# Main.net
KiCad netlist of a schematic drawn in EAGLE
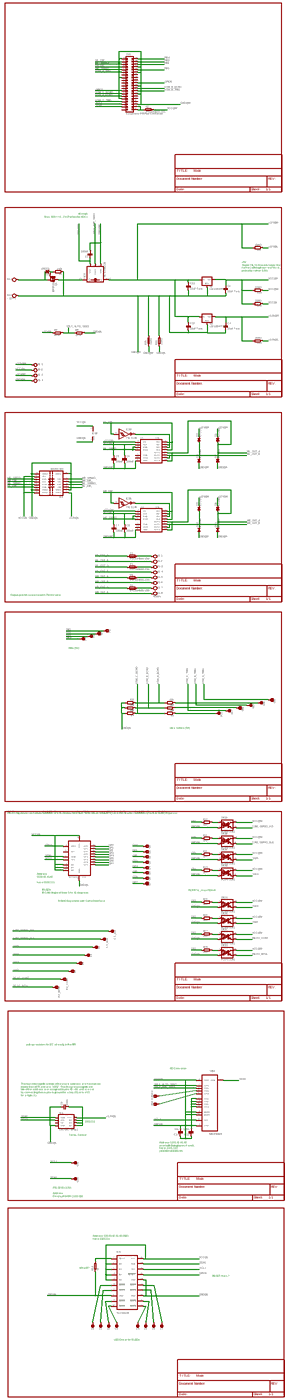
[diagram p0: schematic, sheet 1, overview]
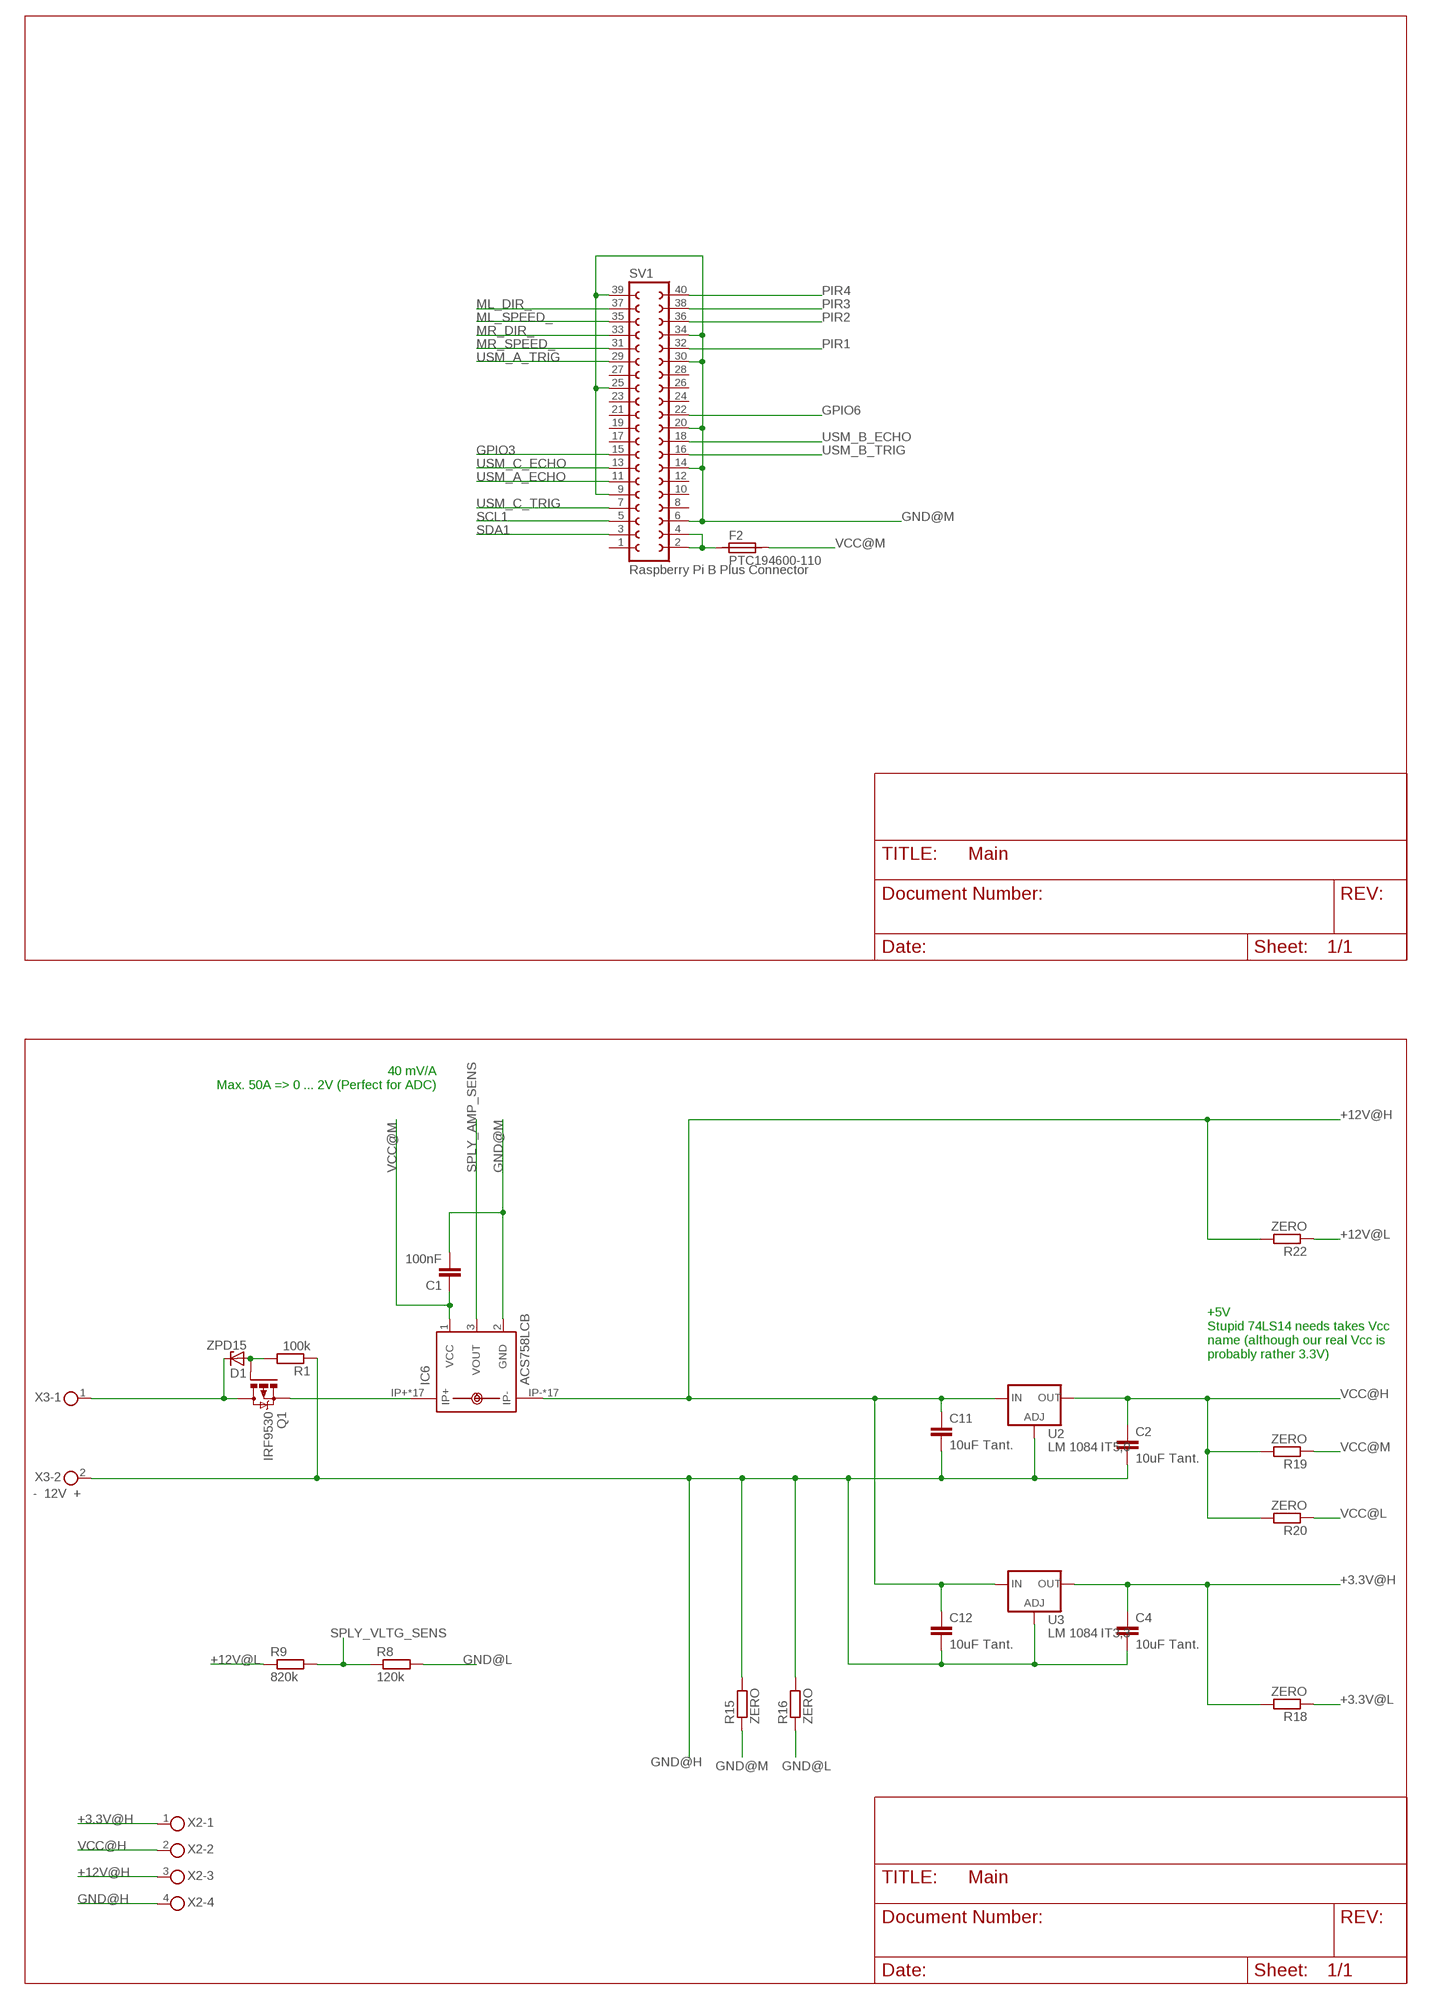
[diagram p1: schematic, sheet 1, part 1 of 4]
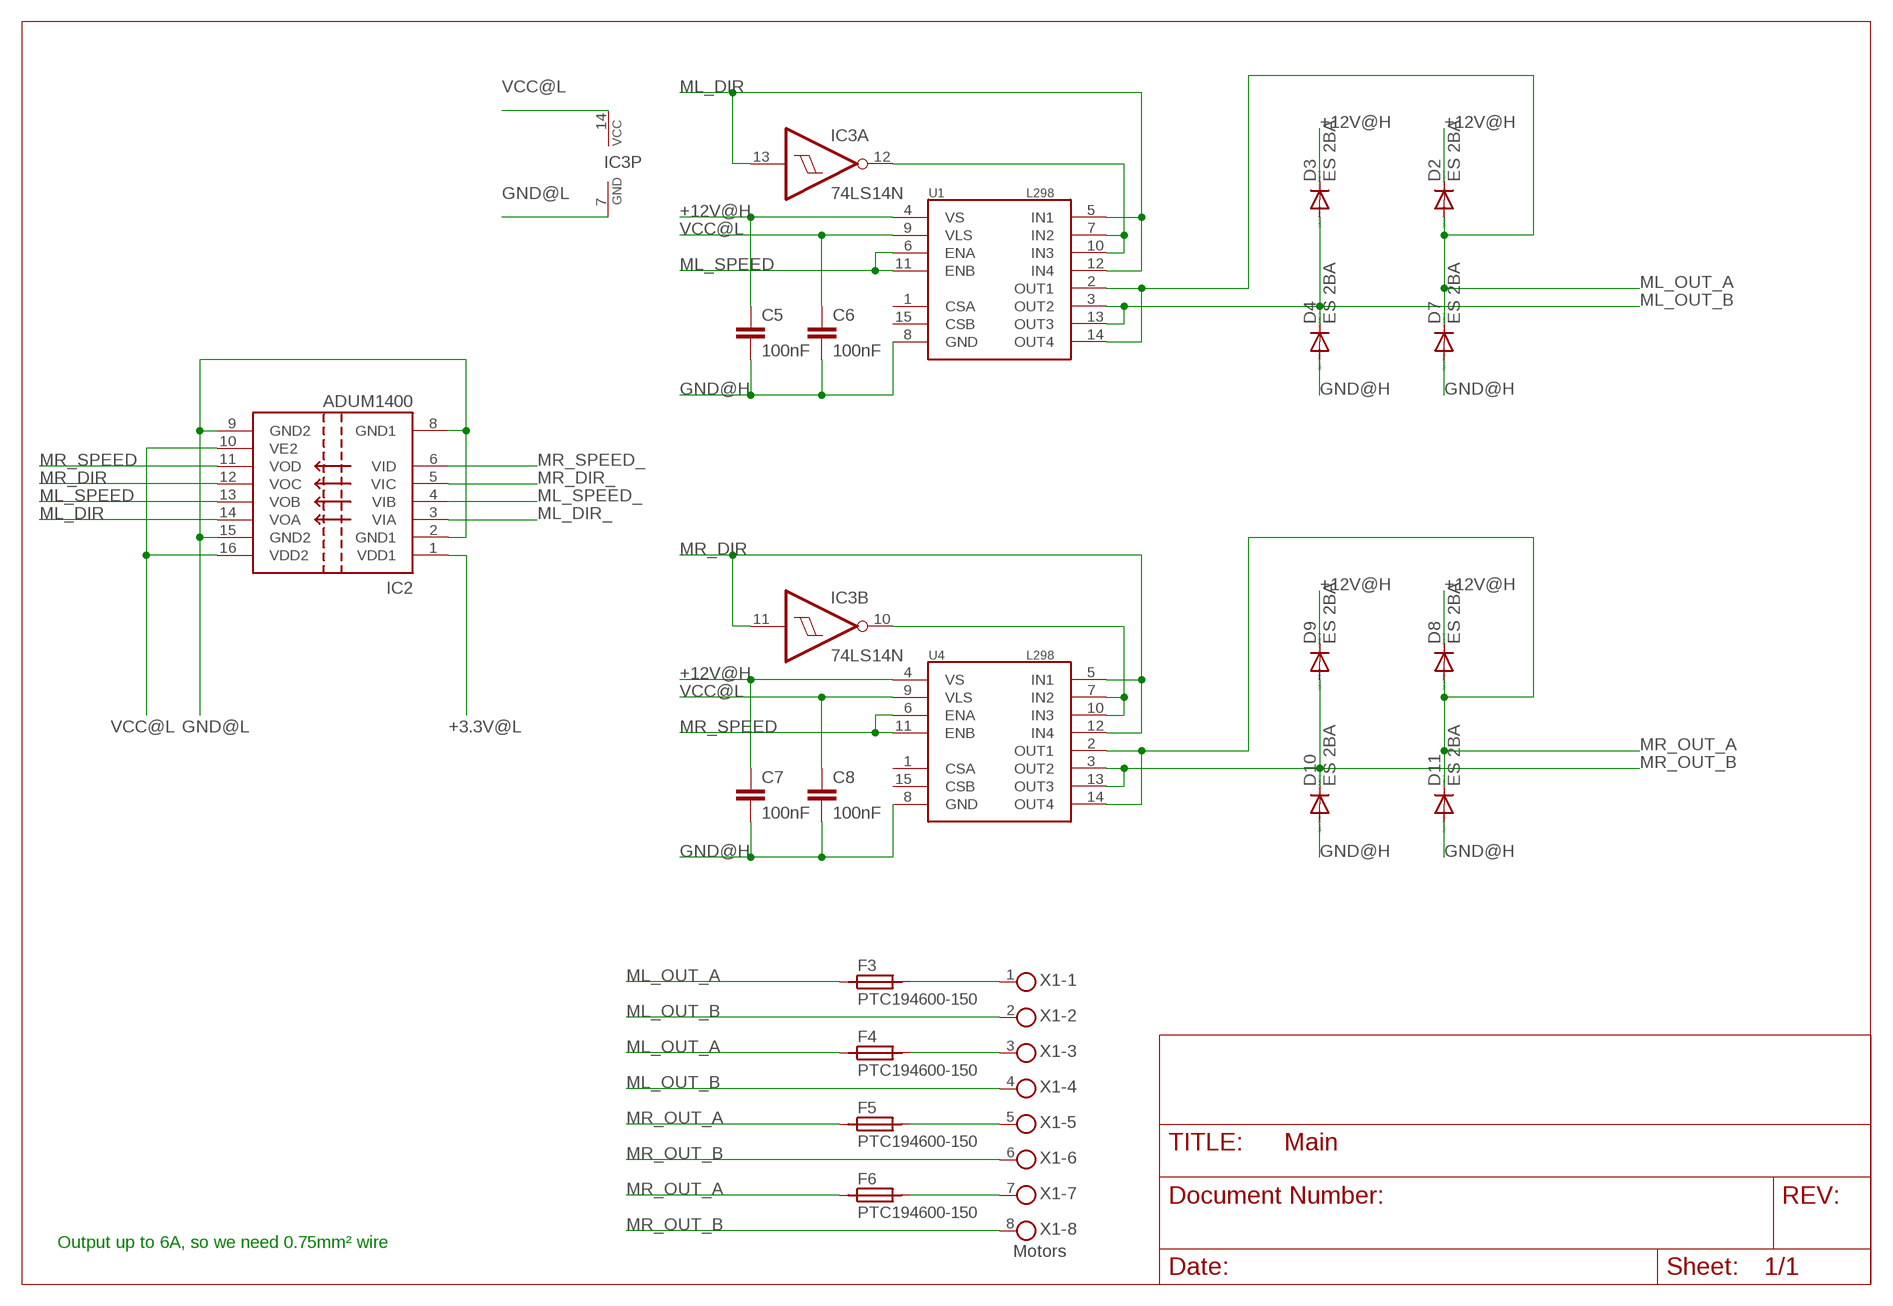
[diagram p2: schematic, sheet 1, part 2 of 4]
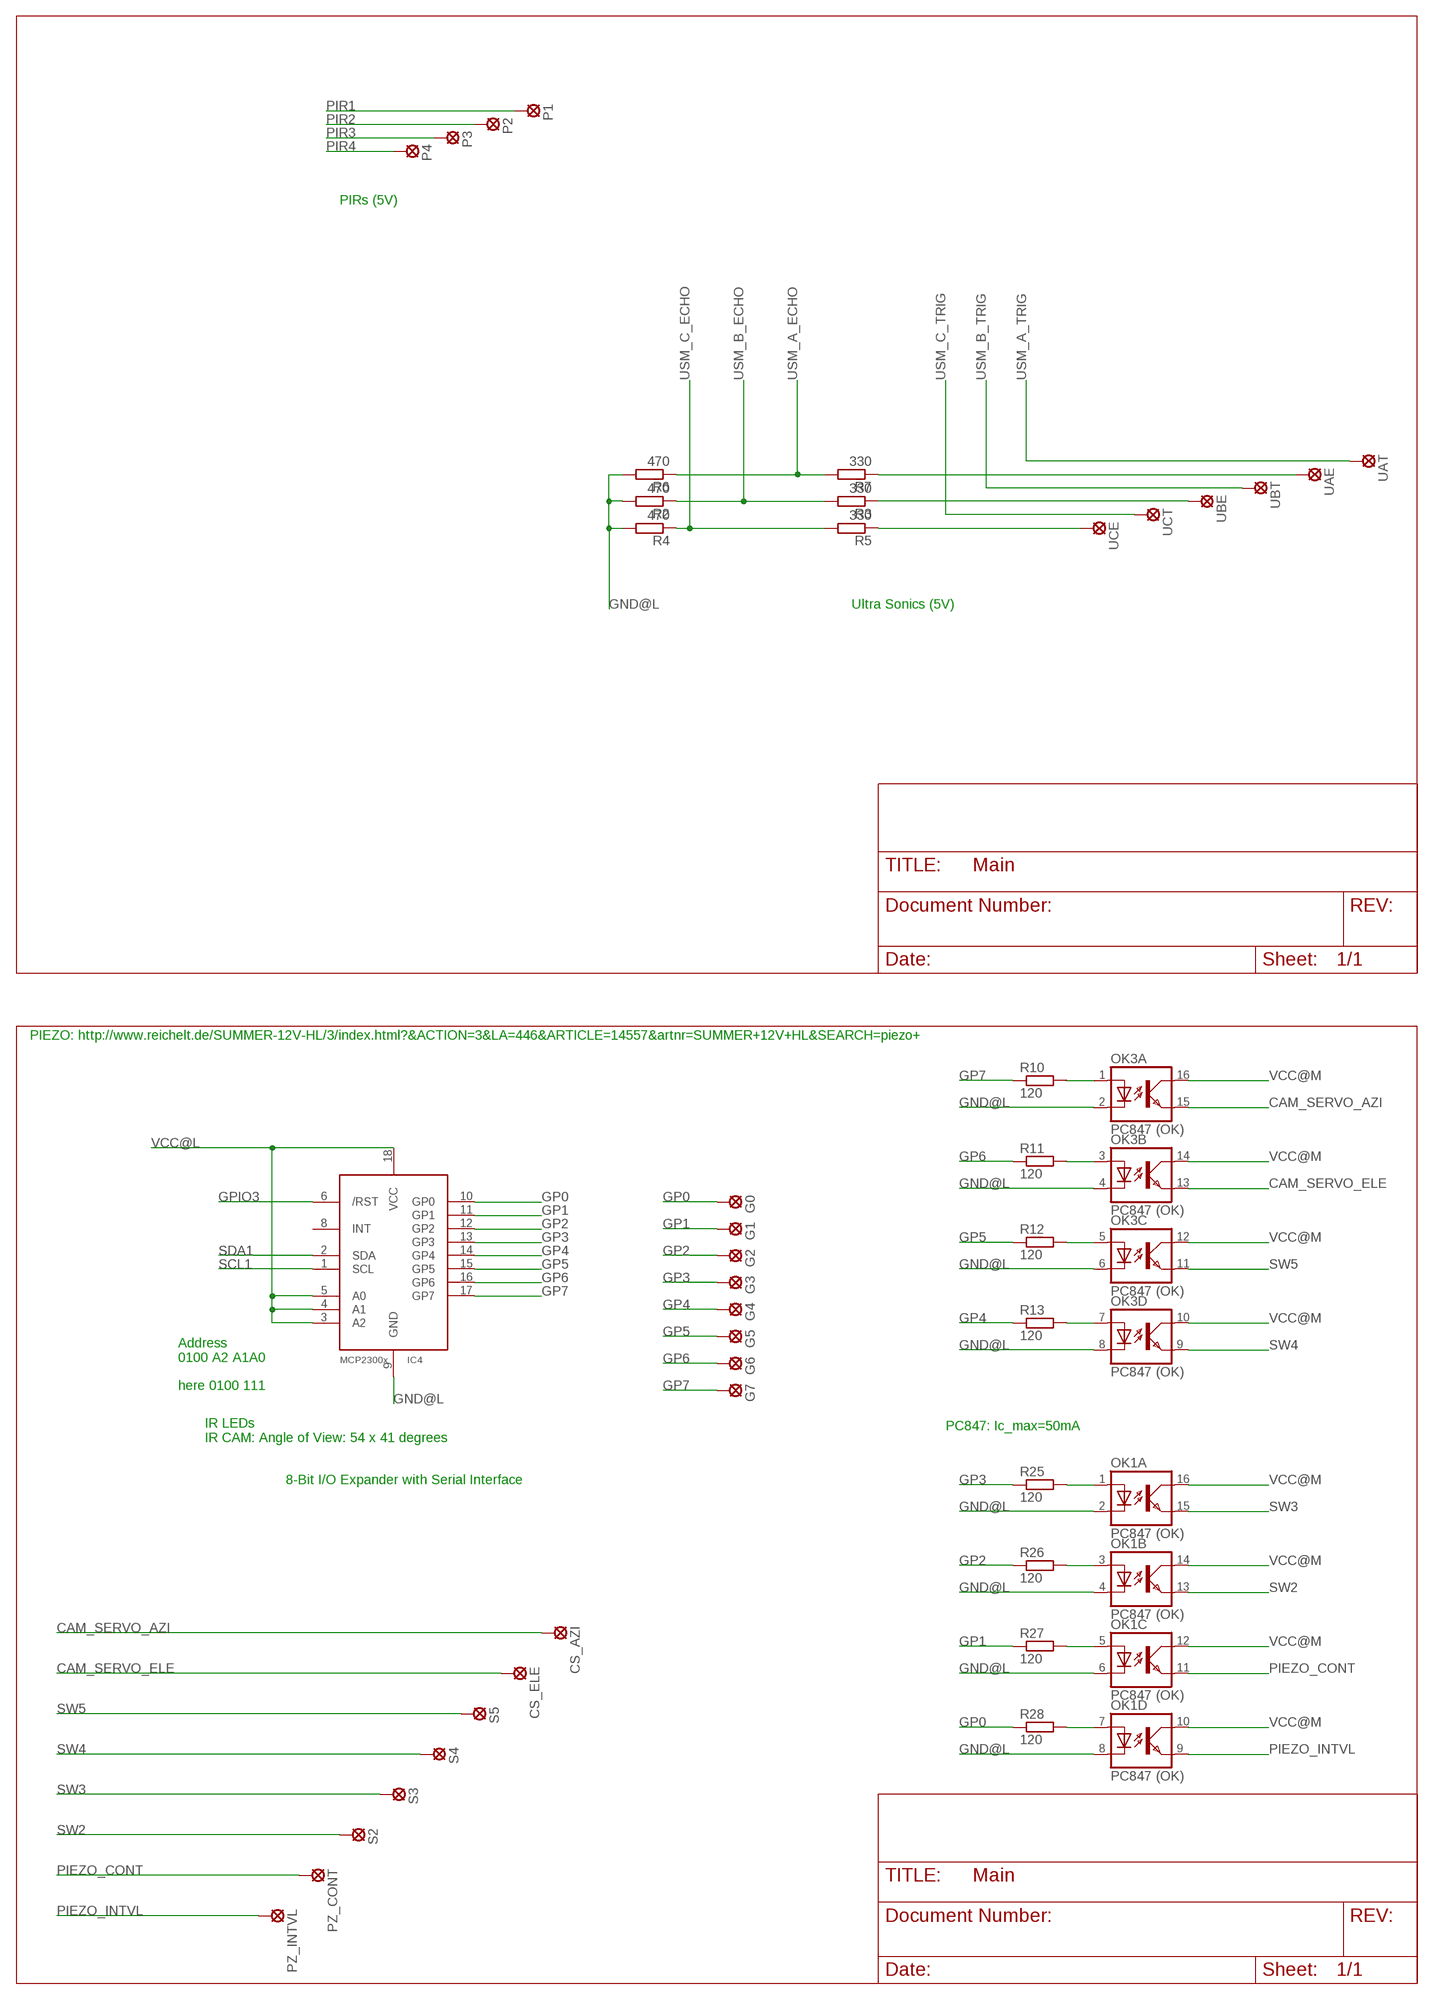
[diagram p3: schematic, sheet 1, part 3 of 4]
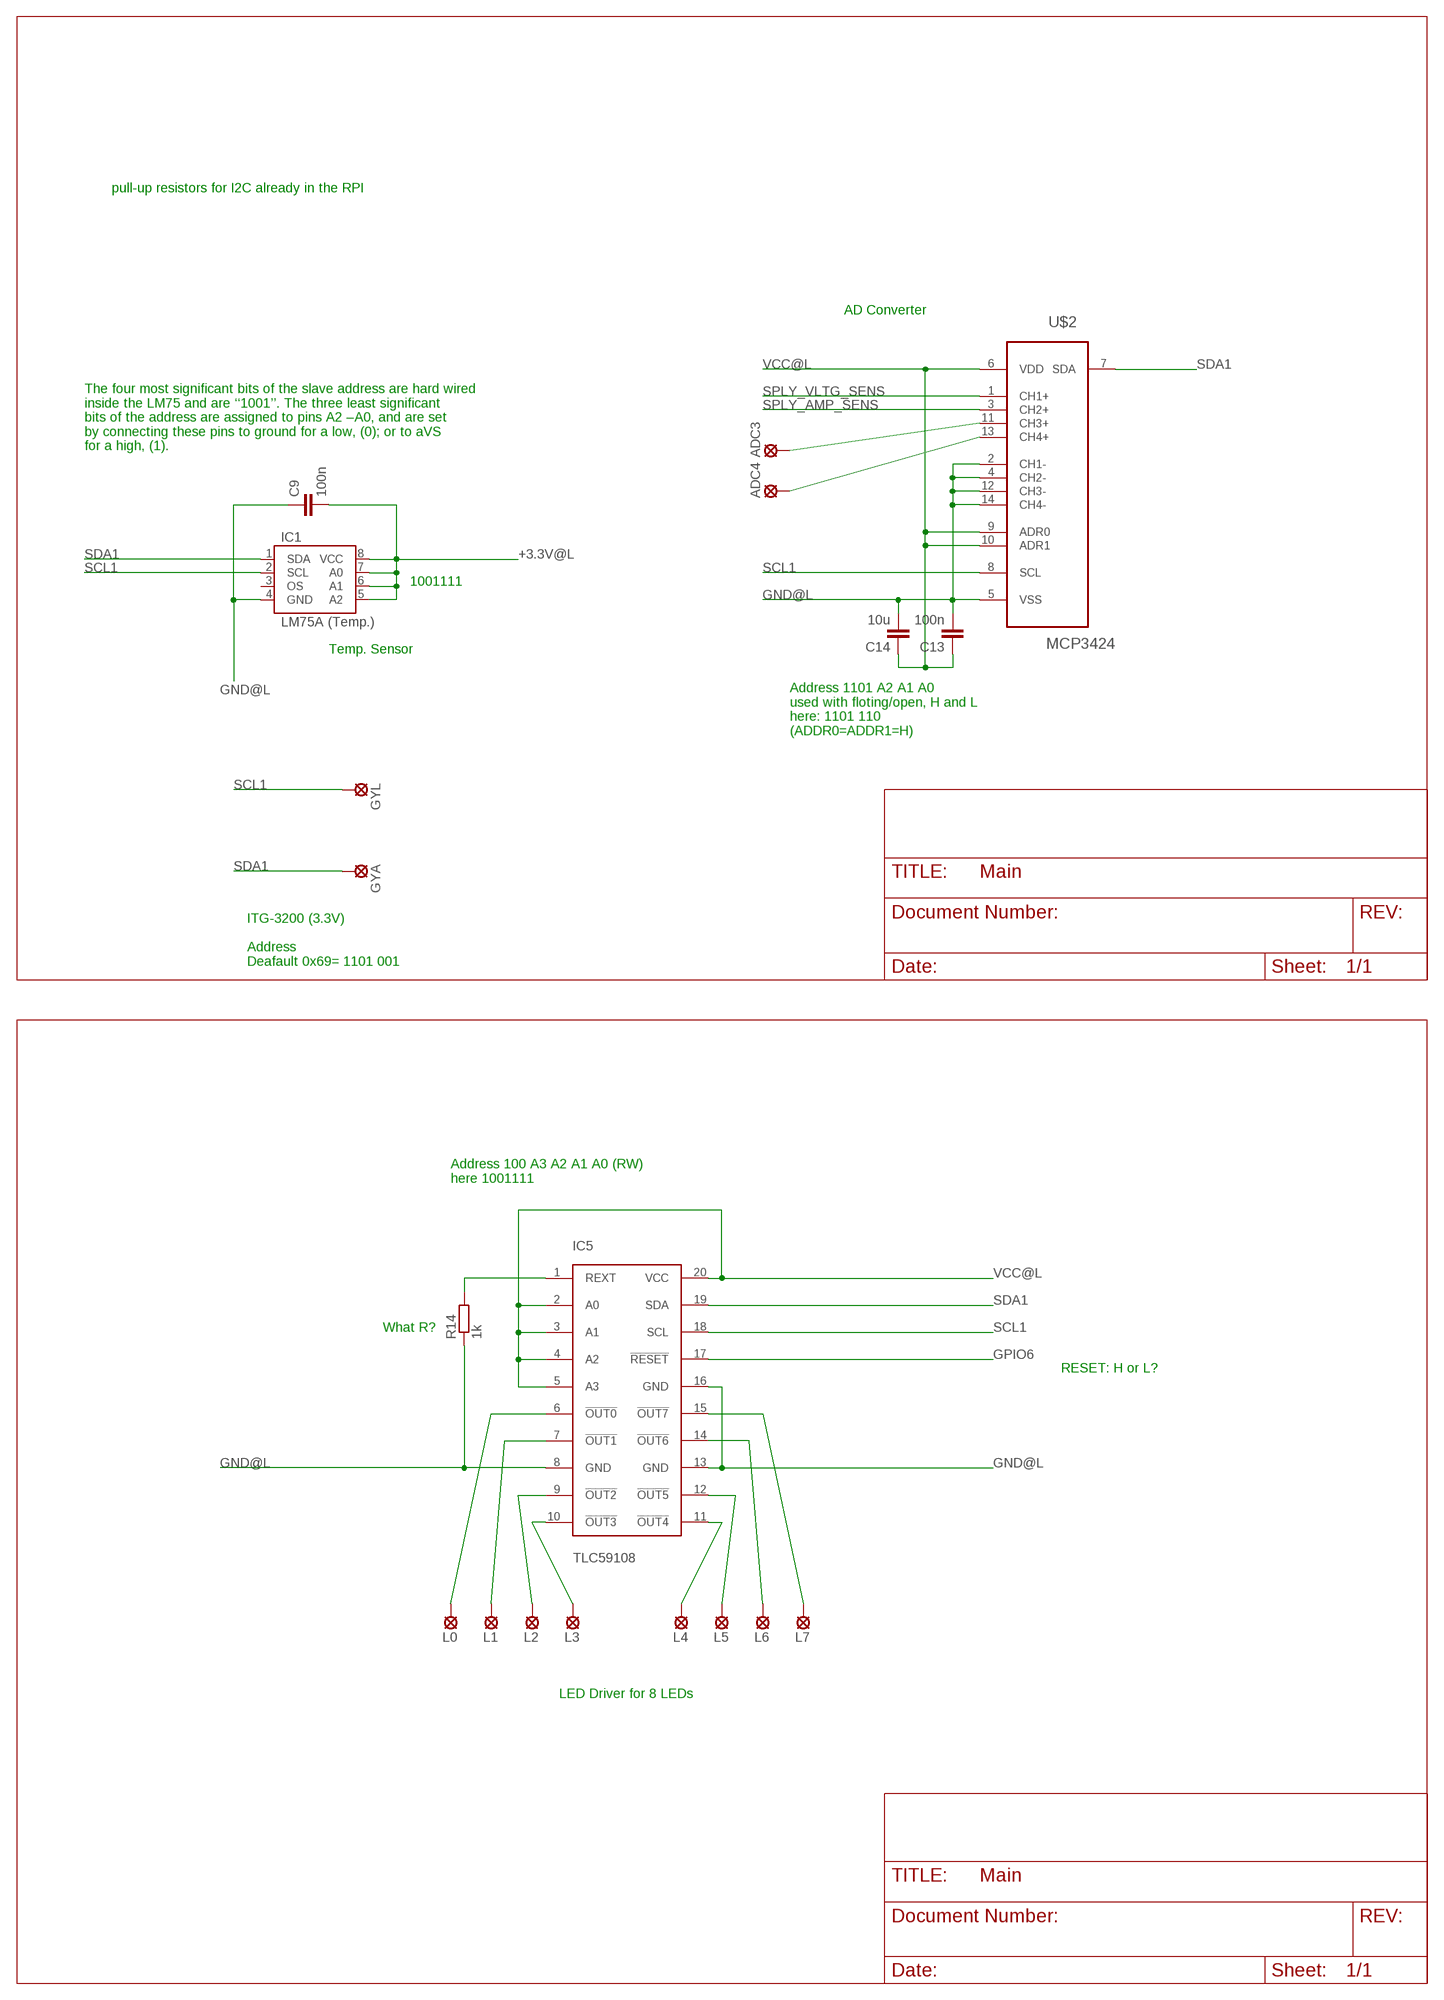
[diagram p4: schematic, sheet 1, part 4 of 4]

(export (version "E")
  (design (tool "Eeschema 10.0.6"))
  (components
    (comp (ref "ADC3")
      (value "LSP10")
      (footprint "eagle-import:LSP10")
      (libsource (lib "eagle-import") (part "LSP10"))
    )
    (comp (ref "ADC4")
      (value "LSP10")
      (footprint "eagle-import:LSP10")
      (libsource (lib "eagle-import") (part "LSP10"))
    )
    (comp (ref "C1")
      (value "100nF")
      (footprint "eagle-import:C0805")
      (libsource (lib "eagle-import") (part "C-EUC0805"))
    )
    (comp (ref "C2")
      (value "10uF Tant.")
      (footprint "eagle-import:C025-040X050")
      (libsource (lib "eagle-import") (part "C-EU025-040X050"))
    )
    (comp (ref "C4")
      (value "10uF Tant.")
      (footprint "eagle-import:C025-040X050")
      (libsource (lib "eagle-import") (part "C-EU025-040X050"))
    )
    (comp (ref "C5")
      (value "100nF")
      (footprint "eagle-import:C0805")
      (libsource (lib "eagle-import") (part "C-EUC0805"))
    )
    (comp (ref "C6")
      (value "100nF")
      (footprint "eagle-import:C0805")
      (libsource (lib "eagle-import") (part "C-EUC0805"))
    )
    (comp (ref "C7")
      (value "100nF")
      (footprint "eagle-import:C0805")
      (libsource (lib "eagle-import") (part "C-EUC0805"))
    )
    (comp (ref "C8")
      (value "100nF")
      (footprint "eagle-import:C0805")
      (libsource (lib "eagle-import") (part "C-EUC0805"))
    )
    (comp (ref "C9")
      (value "100n")
      (footprint "eagle-import:C0805")
      (libsource (lib "eagle-import") (part "C-EUC0805"))
    )
    (comp (ref "C11")
      (value "10uF Tant.")
      (footprint "eagle-import:C025-040X050")
      (libsource (lib "eagle-import") (part "C-EU025-040X050"))
    )
    (comp (ref "C12")
      (value "10uF Tant.")
      (footprint "eagle-import:C025-040X050")
      (libsource (lib "eagle-import") (part "C-EU025-040X050"))
    )
    (comp (ref "C13")
      (value "100n")
      (footprint "eagle-import:C0805")
      (libsource (lib "eagle-import") (part "C-EUC0805"))
    )
    (comp (ref "C14")
      (value "10u")
      (footprint "eagle-import:C0805")
      (libsource (lib "eagle-import") (part "C-EUC0805"))
    )
    (comp (ref "CS_AZI")
      (value "LSP10")
      (footprint "eagle-import:LSP10")
      (libsource (lib "eagle-import") (part "LSP10"))
    )
    (comp (ref "CS_ELE")
      (value "LSP10")
      (footprint "eagle-import:LSP10")
      (libsource (lib "eagle-import") (part "LSP10"))
    )
    (comp (ref "D1")
      (value "ZPD15")
      (footprint "eagle-import:DO35Z10")
      (libsource (lib "eagle-import") (part "ZENER-DIODEDO35Z10"))
    )
    (comp (ref "D2")
      (value "ES 2BA")
      (footprint "eagle-import:SMB")
      (libsource (lib "eagle-import") (part "ES2D"))
    )
    (comp (ref "D3")
      (value "ES 2BA")
      (footprint "eagle-import:SMB")
      (libsource (lib "eagle-import") (part "ES2D"))
    )
    (comp (ref "D4")
      (value "ES 2BA")
      (footprint "eagle-import:SMB")
      (libsource (lib "eagle-import") (part "ES2D"))
    )
    (comp (ref "D7")
      (value "ES 2BA")
      (footprint "eagle-import:SMB")
      (libsource (lib "eagle-import") (part "ES2D"))
    )
    (comp (ref "D8")
      (value "ES 2BA")
      (footprint "eagle-import:SMB")
      (libsource (lib "eagle-import") (part "ES2D"))
    )
    (comp (ref "D9")
      (value "ES 2BA")
      (footprint "eagle-import:SMB")
      (libsource (lib "eagle-import") (part "ES2D"))
    )
    (comp (ref "D10")
      (value "ES 2BA")
      (footprint "eagle-import:SMB")
      (libsource (lib "eagle-import") (part "ES2D"))
    )
    (comp (ref "D11")
      (value "ES 2BA")
      (footprint "eagle-import:SMB")
      (libsource (lib "eagle-import") (part "ES2D"))
    )
    (comp (ref "F2")
      (value "PTC194600-110")
      (footprint "eagle-import:1820")
      (libsource (lib "eagle-import") (part "SIBA194600"))
    )
    (comp (ref "F3")
      (value "PTC194600-150")
      (footprint "eagle-import:1820")
      (libsource (lib "eagle-import") (part "SIBA194600"))
    )
    (comp (ref "F4")
      (value "PTC194600-150")
      (footprint "eagle-import:1820")
      (libsource (lib "eagle-import") (part "SIBA194600"))
    )
    (comp (ref "F5")
      (value "PTC194600-150")
      (footprint "eagle-import:1820")
      (libsource (lib "eagle-import") (part "SIBA194600"))
    )
    (comp (ref "F6")
      (value "PTC194600-150")
      (footprint "eagle-import:1820")
      (libsource (lib "eagle-import") (part "SIBA194600"))
    )
    (comp (ref "G0")
      (value "LSP10")
      (footprint "eagle-import:LSP10")
      (libsource (lib "eagle-import") (part "LSP10"))
    )
    (comp (ref "G1")
      (value "LSP10")
      (footprint "eagle-import:LSP10")
      (libsource (lib "eagle-import") (part "LSP10"))
    )
    (comp (ref "G2")
      (value "LSP10")
      (footprint "eagle-import:LSP10")
      (libsource (lib "eagle-import") (part "LSP10"))
    )
    (comp (ref "G3")
      (value "LSP10")
      (footprint "eagle-import:LSP10")
      (libsource (lib "eagle-import") (part "LSP10"))
    )
    (comp (ref "G4")
      (value "LSP10")
      (footprint "eagle-import:LSP10")
      (libsource (lib "eagle-import") (part "LSP10"))
    )
    (comp (ref "G5")
      (value "LSP10")
      (footprint "eagle-import:LSP10")
      (libsource (lib "eagle-import") (part "LSP10"))
    )
    (comp (ref "G6")
      (value "LSP10")
      (footprint "eagle-import:LSP10")
      (libsource (lib "eagle-import") (part "LSP10"))
    )
    (comp (ref "G7")
      (value "LSP10")
      (footprint "eagle-import:LSP10")
      (libsource (lib "eagle-import") (part "LSP10"))
    )
    (comp (ref "GYA")
      (value "LSP10")
      (footprint "eagle-import:LSP10")
      (libsource (lib "eagle-import") (part "LSP10"))
    )
    (comp (ref "GYL")
      (value "GYRO_SCL")
      (footprint "eagle-import:LSP10")
      (libsource (lib "eagle-import") (part "LSP10"))
    )
    (comp (ref "IC1")
      (value "LM75A (Temp.)")
      (footprint "eagle-import:SO8")
      (libsource (lib "eagle-import") (part "LM75A"))
    )
    (comp (ref "IC2")
      (value "ADUM1400")
      (footprint "eagle-import:SO16W")
      (libsource (lib "eagle-import") (part "ADUM1400"))
    )
    (comp (ref "IC3")
      (value "74LS14N")
      (footprint "eagle-import:DIL14")
      (libsource (lib "eagle-import") (part "7414NLS"))
    )
    (comp (ref "IC4")
      (value "MCP2300X/P")
      (footprint "eagle-import:DIL18")
      (libsource (lib "eagle-import") (part "MCP2300X/P"))
    )
    (comp (ref "IC5")
      (value "TLC59108")
      (footprint "eagle-import:TSSOP20")
      (libsource (lib "eagle-import") (part "TLC59108"))
    )
    (comp (ref "IC6")
      (value "ACS758LCB")
      (footprint "eagle-import:CB-PFF")
      (fields (field (name "MPN") "ACS758LCB-050B-PFF-T"))
      (libsource (lib "eagle-import") (part "ACS758LCB-050B-PFF-T"))
    )
    (comp (ref "L0")
      (value "LSP10")
      (footprint "eagle-import:LSP10")
      (libsource (lib "eagle-import") (part "LSP10"))
    )
    (comp (ref "L1")
      (value "LSP10")
      (footprint "eagle-import:LSP10")
      (libsource (lib "eagle-import") (part "LSP10"))
    )
    (comp (ref "L2")
      (value "LSP10")
      (footprint "eagle-import:LSP10")
      (libsource (lib "eagle-import") (part "LSP10"))
    )
    (comp (ref "L3")
      (value "LSP10")
      (footprint "eagle-import:LSP10")
      (libsource (lib "eagle-import") (part "LSP10"))
    )
    (comp (ref "L4")
      (value "LSP10")
      (footprint "eagle-import:LSP10")
      (libsource (lib "eagle-import") (part "LSP10"))
    )
    (comp (ref "L5")
      (value "LSP10")
      (footprint "eagle-import:LSP10")
      (libsource (lib "eagle-import") (part "LSP10"))
    )
    (comp (ref "L6")
      (value "LSP10")
      (footprint "eagle-import:LSP10")
      (libsource (lib "eagle-import") (part "LSP10"))
    )
    (comp (ref "L7")
      (value "LSP10")
      (footprint "eagle-import:LSP10")
      (libsource (lib "eagle-import") (part "LSP10"))
    )
    (comp (ref "OK1")
      (value "PC847 (OK)")
      (footprint "eagle-import:DIL16")
      (libsource (lib "eagle-import") (part "PC847"))
    )
    (comp (ref "OK3")
      (value "PC847 (OK)")
      (footprint "eagle-import:DIL16")
      (libsource (lib "eagle-import") (part "PC847"))
    )
    (comp (ref "P1")
      (value "LSP10")
      (footprint "eagle-import:LSP10")
      (libsource (lib "eagle-import") (part "LSP10"))
    )
    (comp (ref "P2")
      (value "LSP10")
      (footprint "eagle-import:LSP10")
      (libsource (lib "eagle-import") (part "LSP10"))
    )
    (comp (ref "P3")
      (value "LSP10")
      (footprint "eagle-import:LSP10")
      (libsource (lib "eagle-import") (part "LSP10"))
    )
    (comp (ref "P4")
      (value "LSP10")
      (footprint "eagle-import:LSP10")
      (libsource (lib "eagle-import") (part "LSP10"))
    )
    (comp (ref "PZ_CONT")
      (value "LSP10")
      (footprint "eagle-import:LSP10")
      (libsource (lib "eagle-import") (part "LSP10"))
    )
    (comp (ref "PZ_INTVL")
      (value "LSP10")
      (footprint "eagle-import:LSP10")
      (libsource (lib "eagle-import") (part "LSP10"))
    )
    (comp (ref "Q1")
      (value "IRF9530")
      (footprint "eagle-import:TO220BV")
      (libsource (lib "eagle-import") (part "IRF9530"))
    )
    (comp (ref "R1")
      (value "100k")
      (footprint "eagle-import:R0805")
      (libsource (lib "eagle-import") (part "resistor_R-EU_R0805"))
    )
    (comp (ref "R2")
      (value "470")
      (footprint "eagle-import:R0603")
      (libsource (lib "eagle-import") (part "resistor_R-EU_R0603"))
    )
    (comp (ref "R3")
      (value "330")
      (footprint "eagle-import:R0603")
      (libsource (lib "eagle-import") (part "resistor_R-EU_R0603"))
    )
    (comp (ref "R4")
      (value "470")
      (footprint "eagle-import:R0603")
      (libsource (lib "eagle-import") (part "resistor_R-EU_R0603"))
    )
    (comp (ref "R5")
      (value "330")
      (footprint "eagle-import:R0603")
      (libsource (lib "eagle-import") (part "resistor_R-EU_R0603"))
    )
    (comp (ref "R6")
      (value "470")
      (footprint "eagle-import:R0603")
      (libsource (lib "eagle-import") (part "resistor_R-EU_R0603"))
    )
    (comp (ref "R7")
      (value "330")
      (footprint "eagle-import:R0603")
      (libsource (lib "eagle-import") (part "resistor_R-EU_R0603"))
    )
    (comp (ref "R8")
      (value "120k")
      (footprint "eagle-import:R0603")
      (libsource (lib "eagle-import") (part "rcl-2_R-EU_R0603"))
    )
    (comp (ref "R9")
      (value "820k")
      (footprint "eagle-import:R0603")
      (libsource (lib "eagle-import") (part "rcl-2_R-EU_R0603"))
    )
    (comp (ref "R10")
      (value "120")
      (footprint "eagle-import:R0603")
      (libsource (lib "eagle-import") (part "resistor_R-EU_R0603"))
    )
    (comp (ref "R11")
      (value "120")
      (footprint "eagle-import:R0603")
      (libsource (lib "eagle-import") (part "resistor_R-EU_R0603"))
    )
    (comp (ref "R12")
      (value "120")
      (footprint "eagle-import:R0603")
      (libsource (lib "eagle-import") (part "resistor_R-EU_R0603"))
    )
    (comp (ref "R13")
      (value "120")
      (footprint "eagle-import:R0603")
      (libsource (lib "eagle-import") (part "resistor_R-EU_R0603"))
    )
    (comp (ref "R14")
      (value "1k")
      (footprint "eagle-import:R0603")
      (libsource (lib "eagle-import") (part "R-EU_R0603"))
    )
    (comp (ref "R15")
      (value "ZERO")
      (footprint "eagle-import:0204V")
      (libsource (lib "eagle-import") (part "resistor_R-EU_0204/2V"))
    )
    (comp (ref "R16")
      (value "ZERO")
      (footprint "eagle-import:0204V")
      (libsource (lib "eagle-import") (part "resistor_R-EU_0204/2V"))
    )
    (comp (ref "R18")
      (value "ZERO")
      (footprint "eagle-import:0204V")
      (libsource (lib "eagle-import") (part "resistor_R-EU_0204/2V"))
    )
    (comp (ref "R19")
      (value "ZERO")
      (footprint "eagle-import:0204V")
      (libsource (lib "eagle-import") (part "resistor_R-EU_0204/2V"))
    )
    (comp (ref "R20")
      (value "ZERO")
      (footprint "eagle-import:0204V")
      (libsource (lib "eagle-import") (part "resistor_R-EU_0204/2V"))
    )
    (comp (ref "R22")
      (value "ZERO")
      (footprint "eagle-import:0204V")
      (libsource (lib "eagle-import") (part "resistor_R-EU_0204/2V"))
    )
    (comp (ref "R25")
      (value "120")
      (footprint "eagle-import:R0603")
      (libsource (lib "eagle-import") (part "resistor_R-EU_R0603"))
    )
    (comp (ref "R26")
      (value "120")
      (footprint "eagle-import:R0603")
      (libsource (lib "eagle-import") (part "resistor_R-EU_R0603"))
    )
    (comp (ref "R27")
      (value "120")
      (footprint "eagle-import:R0603")
      (libsource (lib "eagle-import") (part "resistor_R-EU_R0603"))
    )
    (comp (ref "R28")
      (value "120")
      (footprint "eagle-import:R0603")
      (libsource (lib "eagle-import") (part "resistor_R-EU_R0603"))
    )
    (comp (ref "S2")
      (value "LSP10")
      (footprint "eagle-import:LSP10")
      (libsource (lib "eagle-import") (part "LSP10"))
    )
    (comp (ref "S3")
      (value "LSP10")
      (footprint "eagle-import:LSP10")
      (libsource (lib "eagle-import") (part "LSP10"))
    )
    (comp (ref "S4")
      (value "LSP10")
      (footprint "eagle-import:LSP10")
      (libsource (lib "eagle-import") (part "LSP10"))
    )
    (comp (ref "S5")
      (value "LSP10")
      (footprint "eagle-import:LSP10")
      (libsource (lib "eagle-import") (part "LSP10"))
    )
    (comp (ref "SV1")
      (value "Raspberry Pi B Plus Connector")
      (footprint "eagle-import:FE20-2")
      (libsource (lib "eagle-import") (part "FE20-2"))
    )
    (comp (ref "U$2")
      (value "MCP3424")
      (footprint "eagle-import:SOP65P640X120-14N")
      (fields (field (name "MPN") "MCP3424-E/ST"))
      (libsource (lib "eagle-import") (part "MCP3424-E/ST"))
    )
    (comp (ref "U1")
      (value "L298")
      (footprint "eagle-import:MULTIWATT15")
      (libsource (lib "eagle-import") (part "L298"))
    )
    (comp (ref "U2")
      (value "LM 1084 IT5,0")
      (footprint "eagle-import:317TS")
      (libsource (lib "eagle-import") (part "LM1084-V"))
    )
    (comp (ref "U3")
      (value "LM 1084 IT3,3")
      (footprint "eagle-import:317TS")
      (libsource (lib "eagle-import") (part "LM1084-V"))
    )
    (comp (ref "U4")
      (value "L298")
      (footprint "eagle-import:MULTIWATT15")
      (libsource (lib "eagle-import") (part "L298"))
    )
    (comp (ref "UAE")
      (value "LSP10")
      (footprint "eagle-import:LSP10")
      (libsource (lib "eagle-import") (part "LSP10"))
    )
    (comp (ref "UAT")
      (value "LSP10")
      (footprint "eagle-import:LSP10")
      (libsource (lib "eagle-import") (part "LSP10"))
    )
    (comp (ref "UBE")
      (value "LSP10")
      (footprint "eagle-import:LSP10")
      (libsource (lib "eagle-import") (part "LSP10"))
    )
    (comp (ref "UBT")
      (value "LSP10")
      (footprint "eagle-import:LSP10")
      (libsource (lib "eagle-import") (part "LSP10"))
    )
    (comp (ref "UCE")
      (value "LSP10")
      (footprint "eagle-import:LSP10")
      (libsource (lib "eagle-import") (part "LSP10"))
    )
    (comp (ref "UCT")
      (value "LSP10")
      (footprint "eagle-import:LSP10")
      (libsource (lib "eagle-import") (part "LSP10"))
    )
    (comp (ref "X1")
      (value "Motors")
      (footprint "eagle-import:8POL35")
      (libsource (lib "eagle-import") (part "AKL59-08"))
    )
    (comp (ref "X2")
      (value "AKL59-04")
      (footprint "eagle-import:4POL35")
      (libsource (lib "eagle-import") (part "AKL59-04"))
    )
    (comp (ref "X3")
      (value "- 12V +")
      (footprint "eagle-import:2POL35")
      (libsource (lib "eagle-import") (part "AKL59-02"))
    )
  )
  (nets
    (net (code "1") (name "/+3.3V@H") (class "Default")
      (node (ref "C4") (pin "1") (pinfunction "1_1") (pintype "passive"))
      (node (ref "R18") (pin "2") (pinfunction "2_2") (pintype "passive"))
      (node (ref "U3") (pin "2") (pinfunction "OUT_2") (pintype "passive"))
      (node (ref "X2") (pin "1") (pinfunction "1_1") (pintype "passive"))
    )
    (net (code "2") (name "/+3.3V@L") (class "Default")
      (node (ref "C9") (pin "2") (pinfunction "2_2") (pintype "passive"))
      (node (ref "IC1") (pin "5") (pinfunction "A2_5") (pintype "bidirectional"))
      (node (ref "IC1") (pin "6") (pinfunction "A1_6") (pintype "bidirectional"))
      (node (ref "IC1") (pin "7") (pinfunction "A0_7") (pintype "bidirectional"))
      (node (ref "IC1") (pin "8") (pinfunction "VCC_8") (pintype "bidirectional"))
      (node (ref "IC2") (pin "1") (pinfunction "VDD1_1") (pintype "power_in"))
      (node (ref "R18") (pin "1") (pinfunction "1_1") (pintype "passive"))
    )
    (net (code "3") (name "/+12V@H") (class "Default")
      (node (ref "C11") (pin "1") (pinfunction "1_1") (pintype "passive"))
      (node (ref "C12") (pin "1") (pinfunction "1_1") (pintype "passive"))
      (node (ref "C5") (pin "1") (pinfunction "1_1") (pintype "passive"))
      (node (ref "C7") (pin "1") (pinfunction "1_1") (pintype "passive"))
      (node (ref "D2") (pin "C") (pinfunction "C_C") (pintype "passive"))
      (node (ref "D3") (pin "C") (pinfunction "C_C") (pintype "passive"))
      (node (ref "D8") (pin "C") (pinfunction "C_C") (pintype "passive"))
      (node (ref "D9") (pin "C") (pinfunction "C_C") (pintype "passive"))
      (node (ref "IC6") (pin "IP-") (pinfunction "IP-_IP-") (pintype "passive"))
      (node (ref "IC6") (pin "IP-@10") (pinfunction "IP-_IP-@10") (pintype "passive"))
      (node (ref "IC6") (pin "IP-@11") (pinfunction "IP-_IP-@11") (pintype "passive"))
      (node (ref "IC6") (pin "IP-@12") (pinfunction "IP-_IP-@12") (pintype "passive"))
      (node (ref "IC6") (pin "IP-@13") (pinfunction "IP-_IP-@13") (pintype "passive"))
      (node (ref "IC6") (pin "IP-@14") (pinfunction "IP-_IP-@14") (pintype "passive"))
      (node (ref "IC6") (pin "IP-@15") (pinfunction "IP-_IP-@15") (pintype "passive"))
      (node (ref "IC6") (pin "IP-@16") (pinfunction "IP-_IP-@16") (pintype "passive"))
      (node (ref "IC6") (pin "IP-@17") (pinfunction "IP-_IP-@17") (pintype "passive"))
      (node (ref "IC6") (pin "IP-@2") (pinfunction "IP-_IP-@2") (pintype "passive"))
      (node (ref "IC6") (pin "IP-@3") (pinfunction "IP-_IP-@3") (pintype "passive"))
      (node (ref "IC6") (pin "IP-@4") (pinfunction "IP-_IP-@4") (pintype "passive"))
      (node (ref "IC6") (pin "IP-@5") (pinfunction "IP-_IP-@5") (pintype "passive"))
      (node (ref "IC6") (pin "IP-@6") (pinfunction "IP-_IP-@6") (pintype "passive"))
      (node (ref "IC6") (pin "IP-@7") (pinfunction "IP-_IP-@7") (pintype "passive"))
      (node (ref "IC6") (pin "IP-@8") (pinfunction "IP-_IP-@8") (pintype "passive"))
      (node (ref "IC6") (pin "IP-@9") (pinfunction "IP-_IP-@9") (pintype "passive"))
      (node (ref "R22") (pin "2") (pinfunction "2_2") (pintype "passive"))
      (node (ref "U1") (pin "4") (pinfunction "VS_4") (pintype "bidirectional"))
      (node (ref "U2") (pin "3") (pinfunction "IN_3") (pintype "input"))
      (node (ref "U3") (pin "3") (pinfunction "IN_3") (pintype "input"))
      (node (ref "U4") (pin "4") (pinfunction "VS_4") (pintype "bidirectional"))
      (node (ref "X2") (pin "3") (pinfunction "1_3") (pintype "passive"))
    )
    (net (code "4") (name "/+12V@L") (class "Default")
      (node (ref "R22") (pin "1") (pinfunction "1_1") (pintype "passive"))
      (node (ref "R9") (pin "1") (pinfunction "1_1") (pintype "passive"))
    )
    (net (code "5") (name "/CAM_SERVO_AZI") (class "Default")
      (node (ref "CS_AZI") (pin "MP") (pinfunction "MP_MP") (pintype "passive"))
      (node (ref "OK3") (pin "15") (pinfunction "EMIT_15") (pintype "passive"))
    )
    (net (code "6") (name "/CAM_SERVO_ELE") (class "Default")
      (node (ref "CS_ELE") (pin "MP") (pinfunction "MP_MP") (pintype "passive"))
      (node (ref "OK3") (pin "13") (pinfunction "EMIT_13") (pintype "passive"))
    )
    (net (code "7") (name "/GND@H") (class "Default")
      (node (ref "C11") (pin "2") (pinfunction "2_2") (pintype "passive"))
      (node (ref "C12") (pin "2") (pinfunction "2_2") (pintype "passive"))
      (node (ref "C2") (pin "2") (pinfunction "2_2") (pintype "passive"))
      (node (ref "C4") (pin "2") (pinfunction "2_2") (pintype "passive"))
      (node (ref "C5") (pin "2") (pinfunction "2_2") (pintype "passive"))
      (node (ref "C6") (pin "2") (pinfunction "2_2") (pintype "passive"))
      (node (ref "C7") (pin "2") (pinfunction "2_2") (pintype "passive"))
      (node (ref "C8") (pin "2") (pinfunction "2_2") (pintype "passive"))
      (node (ref "D10") (pin "A") (pinfunction "A_A") (pintype "passive"))
      (node (ref "D11") (pin "A") (pinfunction "A_A") (pintype "passive"))
      (node (ref "D4") (pin "A") (pinfunction "A_A") (pintype "passive"))
      (node (ref "D7") (pin "A") (pinfunction "A_A") (pintype "passive"))
      (node (ref "R1") (pin "1") (pinfunction "1_1") (pintype "passive"))
      (node (ref "R15") (pin "2") (pinfunction "2_2") (pintype "passive"))
      (node (ref "R16") (pin "2") (pinfunction "2_2") (pintype "passive"))
      (node (ref "U1") (pin "8") (pinfunction "GND_8") (pintype "bidirectional"))
      (node (ref "U2") (pin "1") (pinfunction "ADJ_1") (pintype "input"))
      (node (ref "U3") (pin "1") (pinfunction "ADJ_1") (pintype "input"))
      (node (ref "U4") (pin "8") (pinfunction "GND_8") (pintype "bidirectional"))
      (node (ref "X2") (pin "4") (pinfunction "1_4") (pintype "passive"))
      (node (ref "X3") (pin "2") (pinfunction "1_2") (pintype "passive"))
    )
    (net (code "8") (name "/GND@L") (class "Default")
      (node (ref "C13") (pin "2") (pinfunction "2_2") (pintype "passive"))
      (node (ref "C14") (pin "2") (pinfunction "2_2") (pintype "passive"))
      (node (ref "C9") (pin "1") (pinfunction "1_1") (pintype "passive"))
      (node (ref "IC1") (pin "4") (pinfunction "GND_4") (pintype "bidirectional"))
      (node (ref "IC2") (pin "15") (pinfunction "GND2_15") (pintype "power_in"))
      (node (ref "IC2") (pin "2") (pinfunction "GND1_2") (pintype "power_in"))
      (node (ref "IC2") (pin "8") (pinfunction "GND1_8") (pintype "power_in"))
      (node (ref "IC2") (pin "9") (pinfunction "GND2_9") (pintype "power_in"))
      (node (ref "IC3") (pin "7") (pinfunction "GND_7") (pintype "power_in"))
      (node (ref "IC4") (pin "9") (pinfunction "GND_9") (pintype "power_in"))
      (node (ref "IC5") (pin "13") (pinfunction "GND_13") (pintype "bidirectional"))
      (node (ref "IC5") (pin "16") (pinfunction "GND_16") (pintype "bidirectional"))
      (node (ref "IC5") (pin "8") (pinfunction "GND_8") (pintype "bidirectional"))
      (node (ref "OK1") (pin "2") (pinfunction "C_2") (pintype "passive"))
      (node (ref "OK1") (pin "4") (pinfunction "C_4") (pintype "passive"))
      (node (ref "OK1") (pin "6") (pinfunction "C_6") (pintype "passive"))
      (node (ref "OK1") (pin "8") (pinfunction "C_8") (pintype "passive"))
      (node (ref "OK3") (pin "2") (pinfunction "C_2") (pintype "passive"))
      (node (ref "OK3") (pin "4") (pinfunction "C_4") (pintype "passive"))
      (node (ref "OK3") (pin "6") (pinfunction "C_6") (pintype "passive"))
      (node (ref "OK3") (pin "8") (pinfunction "C_8") (pintype "passive"))
      (node (ref "R14") (pin "1") (pinfunction "1_1") (pintype "passive"))
      (node (ref "R16") (pin "1") (pinfunction "1_1") (pintype "passive"))
      (node (ref "R2") (pin "2") (pinfunction "2_2") (pintype "passive"))
      (node (ref "R4") (pin "2") (pinfunction "2_2") (pintype "passive"))
      (node (ref "R6") (pin "2") (pinfunction "2_2") (pintype "passive"))
      (node (ref "R8") (pin "2") (pinfunction "2_2") (pintype "passive"))
      (node (ref "U$2") (pin "12") (pinfunction "CH3-_12") (pintype "input"))
      (node (ref "U$2") (pin "14") (pinfunction "CH4-_14") (pintype "input"))
      (node (ref "U$2") (pin "2") (pinfunction "CH1-_2") (pintype "input"))
      (node (ref "U$2") (pin "4") (pinfunction "CH2-_4") (pintype "input"))
      (node (ref "U$2") (pin "5") (pinfunction "VSS_5") (pintype "power_in"))
    )
    (net (code "9") (name "/GND@M") (class "Default")
      (node (ref "C1") (pin "2") (pinfunction "2_2") (pintype "passive"))
      (node (ref "IC6") (pin "2") (pinfunction "GND_2") (pintype "power_in"))
      (node (ref "R15") (pin "1") (pinfunction "1_1") (pintype "passive"))
      (node (ref "SV1") (pin "14") (pinfunction "14_14") (pintype "passive"))
      (node (ref "SV1") (pin "20") (pinfunction "20_20") (pintype "passive"))
      (node (ref "SV1") (pin "25") (pinfunction "25_25") (pintype "passive"))
      (node (ref "SV1") (pin "30") (pinfunction "30_30") (pintype "passive"))
      (node (ref "SV1") (pin "34") (pinfunction "34_34") (pintype "passive"))
      (node (ref "SV1") (pin "39") (pinfunction "39_39") (pintype "passive"))
      (node (ref "SV1") (pin "6") (pinfunction "6_6") (pintype "passive"))
      (node (ref "SV1") (pin "9") (pinfunction "9_9") (pintype "passive"))
    )
    (net (code "10") (name "/GP0") (class "Default")
      (node (ref "G0") (pin "MP") (pinfunction "MP_MP") (pintype "passive"))
      (node (ref "IC4") (pin "10") (pinfunction "GP0_10") (pintype "bidirectional"))
      (node (ref "R28") (pin "1") (pinfunction "1_1") (pintype "passive"))
    )
    (net (code "11") (name "/GP1") (class "Default")
      (node (ref "G1") (pin "MP") (pinfunction "MP_MP") (pintype "passive"))
      (node (ref "IC4") (pin "11") (pinfunction "GP1_11") (pintype "bidirectional"))
      (node (ref "R27") (pin "1") (pinfunction "1_1") (pintype "passive"))
    )
    (net (code "12") (name "/GP2") (class "Default")
      (node (ref "G2") (pin "MP") (pinfunction "MP_MP") (pintype "passive"))
      (node (ref "IC4") (pin "12") (pinfunction "GP2_12") (pintype "bidirectional"))
      (node (ref "R26") (pin "1") (pinfunction "1_1") (pintype "passive"))
    )
    (net (code "13") (name "/GP3") (class "Default")
      (node (ref "G3") (pin "MP") (pinfunction "MP_MP") (pintype "passive"))
      (node (ref "IC4") (pin "13") (pinfunction "GP3_13") (pintype "bidirectional"))
      (node (ref "R25") (pin "1") (pinfunction "1_1") (pintype "passive"))
    )
    (net (code "14") (name "/GP4") (class "Default")
      (node (ref "G4") (pin "MP") (pinfunction "MP_MP") (pintype "passive"))
      (node (ref "IC4") (pin "14") (pinfunction "GP4_14") (pintype "bidirectional"))
      (node (ref "R13") (pin "1") (pinfunction "1_1") (pintype "passive"))
    )
    (net (code "15") (name "/GP5") (class "Default")
      (node (ref "G5") (pin "MP") (pinfunction "MP_MP") (pintype "passive"))
      (node (ref "IC4") (pin "15") (pinfunction "GP5_15") (pintype "bidirectional"))
      (node (ref "R12") (pin "1") (pinfunction "1_1") (pintype "passive"))
    )
    (net (code "16") (name "/GP6") (class "Default")
      (node (ref "G6") (pin "MP") (pinfunction "MP_MP") (pintype "passive"))
      (node (ref "IC4") (pin "16") (pinfunction "GP6_16") (pintype "bidirectional"))
      (node (ref "R11") (pin "1") (pinfunction "1_1") (pintype "passive"))
    )
    (net (code "17") (name "/GP7") (class "Default")
      (node (ref "G7") (pin "MP") (pinfunction "MP_MP") (pintype "passive"))
      (node (ref "IC4") (pin "17") (pinfunction "GP7_17") (pintype "bidirectional"))
      (node (ref "R10") (pin "1") (pinfunction "1_1") (pintype "passive"))
    )
    (net (code "18") (name "/GPIO3") (class "Default")
      (node (ref "IC4") (pin "6") (pinfunction "/RST_6") (pintype "input"))
      (node (ref "SV1") (pin "15") (pinfunction "15_15") (pintype "passive"))
    )
    (net (code "19") (name "/GPIO6") (class "Default")
      (node (ref "IC5") (pin "17") (pinfunction "~{RESET}_17") (pintype "bidirectional"))
      (node (ref "SV1") (pin "22") (pinfunction "22_22") (pintype "passive"))
    )
    (net (code "20") (name "/ML_DIR") (class "Default")
      (node (ref "IC2") (pin "14") (pinfunction "VOA_14") (pintype "output"))
      (node (ref "IC3") (pin "13") (pinfunction "I_13") (pintype "input"))
      (node (ref "U1") (pin "12") (pinfunction "IN4_12") (pintype "bidirectional"))
      (node (ref "U1") (pin "5") (pinfunction "IN1_5") (pintype "bidirectional"))
    )
    (net (code "21") (name "/ML_DIR_") (class "Default")
      (node (ref "IC2") (pin "3") (pinfunction "VIA_3") (pintype "input"))
      (node (ref "SV1") (pin "37") (pinfunction "37_37") (pintype "passive"))
    )
    (net (code "22") (name "/ML_OUT_A") (class "Default")
      (node (ref "D2") (pin "A") (pinfunction "A_A") (pintype "passive"))
      (node (ref "D7") (pin "C") (pinfunction "C_C") (pintype "passive"))
      (node (ref "F3") (pin "1") (pinfunction "1_1") (pintype "passive"))
      (node (ref "F4") (pin "1") (pinfunction "1_1") (pintype "passive"))
      (node (ref "U1") (pin "14") (pinfunction "OUT4_14") (pintype "bidirectional"))
      (node (ref "U1") (pin "2") (pinfunction "OUT1_2") (pintype "bidirectional"))
    )
    (net (code "23") (name "/ML_OUT_B") (class "Default")
      (node (ref "D3") (pin "A") (pinfunction "A_A") (pintype "passive"))
      (node (ref "D4") (pin "C") (pinfunction "C_C") (pintype "passive"))
      (node (ref "U1") (pin "13") (pinfunction "OUT3_13") (pintype "bidirectional"))
      (node (ref "U1") (pin "3") (pinfunction "OUT2_3") (pintype "bidirectional"))
      (node (ref "X1") (pin "2") (pinfunction "1_2") (pintype "passive"))
      (node (ref "X1") (pin "4") (pinfunction "1_4") (pintype "passive"))
    )
    (net (code "24") (name "/ML_SPEED") (class "Default")
      (node (ref "IC2") (pin "13") (pinfunction "VOB_13") (pintype "output"))
      (node (ref "U1") (pin "11") (pinfunction "ENB_11") (pintype "bidirectional"))
      (node (ref "U1") (pin "6") (pinfunction "ENA_6") (pintype "bidirectional"))
    )
    (net (code "25") (name "/ML_SPEED_") (class "Default")
      (node (ref "IC2") (pin "4") (pinfunction "VIB_4") (pintype "input"))
      (node (ref "SV1") (pin "35") (pinfunction "35_35") (pintype "passive"))
    )
    (net (code "26") (name "/MR_DIR") (class "Default")
      (node (ref "IC2") (pin "12") (pinfunction "VOC_12") (pintype "output"))
      (node (ref "IC3") (pin "11") (pinfunction "I_11") (pintype "input"))
      (node (ref "U4") (pin "12") (pinfunction "IN4_12") (pintype "bidirectional"))
      (node (ref "U4") (pin "5") (pinfunction "IN1_5") (pintype "bidirectional"))
    )
    (net (code "27") (name "/MR_DIR_") (class "Default")
      (node (ref "IC2") (pin "5") (pinfunction "VIC_5") (pintype "input"))
      (node (ref "SV1") (pin "33") (pinfunction "33_33") (pintype "passive"))
    )
    (net (code "28") (name "/MR_OUT_A") (class "Default")
      (node (ref "D11") (pin "C") (pinfunction "C_C") (pintype "passive"))
      (node (ref "D8") (pin "A") (pinfunction "A_A") (pintype "passive"))
      (node (ref "F5") (pin "1") (pinfunction "1_1") (pintype "passive"))
      (node (ref "F6") (pin "1") (pinfunction "1_1") (pintype "passive"))
      (node (ref "U4") (pin "14") (pinfunction "OUT4_14") (pintype "bidirectional"))
      (node (ref "U4") (pin "2") (pinfunction "OUT1_2") (pintype "bidirectional"))
    )
    (net (code "29") (name "/MR_OUT_B") (class "Default")
      (node (ref "D10") (pin "C") (pinfunction "C_C") (pintype "passive"))
      (node (ref "D9") (pin "A") (pinfunction "A_A") (pintype "passive"))
      (node (ref "U4") (pin "13") (pinfunction "OUT3_13") (pintype "bidirectional"))
      (node (ref "U4") (pin "3") (pinfunction "OUT2_3") (pintype "bidirectional"))
      (node (ref "X1") (pin "6") (pinfunction "1_6") (pintype "passive"))
      (node (ref "X1") (pin "8") (pinfunction "1_8") (pintype "passive"))
    )
    (net (code "30") (name "/MR_SPEED") (class "Default")
      (node (ref "IC2") (pin "11") (pinfunction "VOD_11") (pintype "output"))
      (node (ref "U4") (pin "11") (pinfunction "ENB_11") (pintype "bidirectional"))
      (node (ref "U4") (pin "6") (pinfunction "ENA_6") (pintype "bidirectional"))
    )
    (net (code "31") (name "/MR_SPEED_") (class "Default")
      (node (ref "IC2") (pin "6") (pinfunction "VID_6") (pintype "input"))
      (node (ref "SV1") (pin "31") (pinfunction "31_31") (pintype "passive"))
    )
    (net (code "32") (name "/PIEZO_CONT") (class "Default")
      (node (ref "OK1") (pin "11") (pinfunction "EMIT_11") (pintype "passive"))
      (node (ref "PZ_CONT") (pin "MP") (pinfunction "MP_MP") (pintype "passive"))
    )
    (net (code "33") (name "/PIEZO_INTVL") (class "Default")
      (node (ref "OK1") (pin "9") (pinfunction "EMIT_9") (pintype "passive"))
      (node (ref "PZ_INTVL") (pin "MP") (pinfunction "MP_MP") (pintype "passive"))
    )
    (net (code "34") (name "/PIR1") (class "Default")
      (node (ref "P1") (pin "MP") (pinfunction "MP_MP") (pintype "passive"))
      (node (ref "SV1") (pin "32") (pinfunction "32_32") (pintype "passive"))
    )
    (net (code "35") (name "/PIR2") (class "Default")
      (node (ref "P2") (pin "MP") (pinfunction "MP_MP") (pintype "passive"))
      (node (ref "SV1") (pin "36") (pinfunction "36_36") (pintype "passive"))
    )
    (net (code "36") (name "/PIR3") (class "Default")
      (node (ref "P3") (pin "MP") (pinfunction "MP_MP") (pintype "passive"))
      (node (ref "SV1") (pin "38") (pinfunction "38_38") (pintype "passive"))
    )
    (net (code "37") (name "/PIR4") (class "Default")
      (node (ref "P4") (pin "MP") (pinfunction "MP_MP") (pintype "passive"))
      (node (ref "SV1") (pin "40") (pinfunction "40_40") (pintype "passive"))
    )
    (net (code "38") (name "/SCL1") (class "Default")
      (node (ref "GYL") (pin "MP") (pinfunction "MP_MP") (pintype "passive"))
      (node (ref "IC1") (pin "2") (pinfunction "SCL_2") (pintype "bidirectional"))
      (node (ref "IC4") (pin "1") (pinfunction "SCL_1") (pintype "bidirectional"))
      (node (ref "IC5") (pin "18") (pinfunction "SCL_18") (pintype "bidirectional"))
      (node (ref "SV1") (pin "5") (pinfunction "5_5") (pintype "passive"))
      (node (ref "U$2") (pin "8") (pinfunction "SCL_8") (pintype "input"))
    )
    (net (code "39") (name "/SDA1") (class "Default")
      (node (ref "GYA") (pin "MP") (pinfunction "MP_MP") (pintype "passive"))
      (node (ref "IC1") (pin "1") (pinfunction "SDA_1") (pintype "bidirectional"))
      (node (ref "IC4") (pin "2") (pinfunction "SDA_2") (pintype "bidirectional"))
      (node (ref "IC5") (pin "19") (pinfunction "SDA_19") (pintype "bidirectional"))
      (node (ref "SV1") (pin "3") (pinfunction "3_3") (pintype "passive"))
      (node (ref "U$2") (pin "7") (pinfunction "SDA_7") (pintype "bidirectional"))
    )
    (net (code "40") (name "/SPLY_AMP_SENS") (class "Default")
      (node (ref "IC6") (pin "3") (pinfunction "VOUT_3") (pintype "output"))
      (node (ref "U$2") (pin "3") (pinfunction "CH2+_3") (pintype "input"))
    )
    (net (code "41") (name "/SPLY_VLTG_SENS") (class "Default")
      (node (ref "R8") (pin "1") (pinfunction "1_1") (pintype "passive"))
      (node (ref "R9") (pin "2") (pinfunction "2_2") (pintype "passive"))
      (node (ref "U$2") (pin "1") (pinfunction "CH1+_1") (pintype "input"))
    )
    (net (code "42") (name "/SW2") (class "Default")
      (node (ref "OK1") (pin "13") (pinfunction "EMIT_13") (pintype "passive"))
      (node (ref "S2") (pin "MP") (pinfunction "MP_MP") (pintype "passive"))
    )
    (net (code "43") (name "/SW3") (class "Default")
      (node (ref "OK1") (pin "15") (pinfunction "EMIT_15") (pintype "passive"))
      (node (ref "S3") (pin "MP") (pinfunction "MP_MP") (pintype "passive"))
    )
    (net (code "44") (name "/SW4") (class "Default")
      (node (ref "OK3") (pin "9") (pinfunction "EMIT_9") (pintype "passive"))
      (node (ref "S4") (pin "MP") (pinfunction "MP_MP") (pintype "passive"))
    )
    (net (code "45") (name "/SW5") (class "Default")
      (node (ref "OK3") (pin "11") (pinfunction "EMIT_11") (pintype "passive"))
      (node (ref "S5") (pin "MP") (pinfunction "MP_MP") (pintype "passive"))
    )
    (net (code "46") (name "/USM_A_ECHO") (class "Default")
      (node (ref "R6") (pin "1") (pinfunction "1_1") (pintype "passive"))
      (node (ref "R7") (pin "2") (pinfunction "2_2") (pintype "passive"))
      (node (ref "SV1") (pin "11") (pinfunction "11_11") (pintype "passive"))
    )
    (net (code "47") (name "/USM_A_TRIG") (class "Default")
      (node (ref "SV1") (pin "29") (pinfunction "29_29") (pintype "passive"))
      (node (ref "UAT") (pin "MP") (pinfunction "MP_MP") (pintype "passive"))
    )
    (net (code "48") (name "/USM_B_ECHO") (class "Default")
      (node (ref "R2") (pin "1") (pinfunction "1_1") (pintype "passive"))
      (node (ref "R3") (pin "2") (pinfunction "2_2") (pintype "passive"))
      (node (ref "SV1") (pin "18") (pinfunction "18_18") (pintype "passive"))
    )
    (net (code "49") (name "/USM_B_TRIG") (class "Default")
      (node (ref "SV1") (pin "16") (pinfunction "16_16") (pintype "passive"))
      (node (ref "UBT") (pin "MP") (pinfunction "MP_MP") (pintype "passive"))
    )
    (net (code "50") (name "/USM_C_ECHO") (class "Default")
      (node (ref "R4") (pin "1") (pinfunction "1_1") (pintype "passive"))
      (node (ref "R5") (pin "2") (pinfunction "2_2") (pintype "passive"))
      (node (ref "SV1") (pin "13") (pinfunction "13_13") (pintype "passive"))
    )
    (net (code "51") (name "/USM_C_TRIG") (class "Default")
      (node (ref "SV1") (pin "7") (pinfunction "7_7") (pintype "passive"))
      (node (ref "UCT") (pin "MP") (pinfunction "MP_MP") (pintype "passive"))
    )
    (net (code "52") (name "/VCC@H") (class "Default")
      (node (ref "C2") (pin "1") (pinfunction "1_1") (pintype "passive"))
      (node (ref "R19") (pin "2") (pinfunction "2_2") (pintype "passive"))
      (node (ref "R20") (pin "2") (pinfunction "2_2") (pintype "passive"))
      (node (ref "U2") (pin "2") (pinfunction "OUT_2") (pintype "passive"))
      (node (ref "X2") (pin "2") (pinfunction "1_2") (pintype "passive"))
    )
    (net (code "53") (name "/VCC@L") (class "Default")
      (node (ref "C13") (pin "1") (pinfunction "1_1") (pintype "passive"))
      (node (ref "C14") (pin "1") (pinfunction "1_1") (pintype "passive"))
      (node (ref "C6") (pin "1") (pinfunction "1_1") (pintype "passive"))
      (node (ref "C8") (pin "1") (pinfunction "1_1") (pintype "passive"))
      (node (ref "IC2") (pin "10") (pinfunction "VE2_10") (pintype "passive"))
      (node (ref "IC2") (pin "16") (pinfunction "VDD2_16") (pintype "power_in"))
      (node (ref "IC3") (pin "14") (pinfunction "VCC_14") (pintype "power_in"))
      (node (ref "IC4") (pin "18") (pinfunction "VCC_18") (pintype "power_in"))
      (node (ref "IC4") (pin "3") (pinfunction "A2_3") (pintype "input"))
      (node (ref "IC4") (pin "4") (pinfunction "A1_4") (pintype "input"))
      (node (ref "IC4") (pin "5") (pinfunction "A0_5") (pintype "input"))
      (node (ref "IC5") (pin "2") (pinfunction "A0_2") (pintype "bidirectional"))
      (node (ref "IC5") (pin "20") (pinfunction "VCC_20") (pintype "bidirectional"))
      (node (ref "IC5") (pin "3") (pinfunction "A1_3") (pintype "bidirectional"))
      (node (ref "IC5") (pin "4") (pinfunction "A2_4") (pintype "bidirectional"))
      (node (ref "IC5") (pin "5") (pinfunction "A3_5") (pintype "bidirectional"))
      (node (ref "R20") (pin "1") (pinfunction "1_1") (pintype "passive"))
      (node (ref "U$2") (pin "10") (pinfunction "ADR1_10") (pintype "input"))
      (node (ref "U$2") (pin "6") (pinfunction "VDD_6") (pintype "power_in"))
      (node (ref "U$2") (pin "9") (pinfunction "ADR0_9") (pintype "input"))
      (node (ref "U1") (pin "9") (pinfunction "VLS_9") (pintype "bidirectional"))
      (node (ref "U4") (pin "9") (pinfunction "VLS_9") (pintype "bidirectional"))
    )
    (net (code "54") (name "/VCC@M") (class "Default")
      (node (ref "C1") (pin "1") (pinfunction "1_1") (pintype "passive"))
      (node (ref "F2") (pin "2") (pinfunction "2_2") (pintype "passive"))
      (node (ref "IC6") (pin "1") (pinfunction "VCC_1") (pintype "power_in"))
      (node (ref "OK1") (pin "10") (pinfunction "COL_10") (pintype "passive"))
      (node (ref "OK1") (pin "12") (pinfunction "COL_12") (pintype "passive"))
      (node (ref "OK1") (pin "14") (pinfunction "COL_14") (pintype "passive"))
      (node (ref "OK1") (pin "16") (pinfunction "COL_16") (pintype "passive"))
      (node (ref "OK3") (pin "10") (pinfunction "COL_10") (pintype "passive"))
      (node (ref "OK3") (pin "12") (pinfunction "COL_12") (pintype "passive"))
      (node (ref "OK3") (pin "14") (pinfunction "COL_14") (pintype "passive"))
      (node (ref "OK3") (pin "16") (pinfunction "COL_16") (pintype "passive"))
      (node (ref "R19") (pin "1") (pinfunction "1_1") (pintype "passive"))
    )
    (net (code "55") (name "Net-(D1-PadA)") (class "Default")
      (node (ref "D1") (pin "A") (pinfunction "A_A") (pintype "passive"))
      (node (ref "Q1") (pin "G") (pinfunction "G_G") (pintype "passive"))
      (node (ref "R1") (pin "2") (pinfunction "2_2") (pintype "passive"))
    )
    (net (code "56") (name "Net-(D1-PadC)") (class "Default")
      (node (ref "D1") (pin "C") (pinfunction "C_C") (pintype "passive"))
      (node (ref "Q1") (pin "D") (pinfunction "D_D") (pintype "passive"))
      (node (ref "X3") (pin "1") (pinfunction "1_1") (pintype "passive"))
    )
    (net (code "57") (name "Net-(F2-Pad1)") (class "Default")
      (node (ref "F2") (pin "1") (pinfunction "1_1") (pintype "passive"))
      (node (ref "SV1") (pin "2") (pinfunction "2_2") (pintype "passive"))
      (node (ref "SV1") (pin "4") (pinfunction "4_4") (pintype "passive"))
    )
    (net (code "58") (name "Net-(F3-Pad2)") (class "Default")
      (node (ref "F3") (pin "2") (pinfunction "2_2") (pintype "passive"))
      (node (ref "X1") (pin "1") (pinfunction "1_1") (pintype "passive"))
    )
    (net (code "59") (name "Net-(IC3A-O)") (class "Default")
      (node (ref "IC3") (pin "12") (pinfunction "O_12") (pintype "output"))
      (node (ref "U1") (pin "10") (pinfunction "IN3_10") (pintype "bidirectional"))
      (node (ref "U1") (pin "7") (pinfunction "IN2_7") (pintype "bidirectional"))
    )
    (net (code "60") (name "Net-(IC3B-O)") (class "Default")
      (node (ref "IC3") (pin "10") (pinfunction "O_10") (pintype "output"))
      (node (ref "U4") (pin "10") (pinfunction "IN3_10") (pintype "bidirectional"))
      (node (ref "U4") (pin "7") (pinfunction "IN2_7") (pintype "bidirectional"))
    )
    (net (code "61") (name "Net-(IC5-REXT)") (class "Default")
      (node (ref "IC5") (pin "1") (pinfunction "REXT_1") (pintype "bidirectional"))
      (node (ref "R14") (pin "2") (pinfunction "2_2") (pintype "passive"))
    )
    (net (code "62") (name "Net-(IC5-~{OUT0})") (class "Default")
      (node (ref "IC5") (pin "6") (pinfunction "~{OUT0}_6") (pintype "bidirectional"))
      (node (ref "L0") (pin "MP") (pinfunction "MP_MP") (pintype "passive"))
    )
    (net (code "63") (name "Net-(IC5-~{OUT1})") (class "Default")
      (node (ref "IC5") (pin "7") (pinfunction "~{OUT1}_7") (pintype "bidirectional"))
      (node (ref "L1") (pin "MP") (pinfunction "MP_MP") (pintype "passive"))
    )
    (net (code "64") (name "Net-(IC5-~{OUT2})") (class "Default")
      (node (ref "IC5") (pin "9") (pinfunction "~{OUT2}_9") (pintype "bidirectional"))
      (node (ref "L2") (pin "MP") (pinfunction "MP_MP") (pintype "passive"))
    )
    (net (code "65") (name "Net-(IC5-~{OUT3})") (class "Default")
      (node (ref "IC5") (pin "10") (pinfunction "~{OUT3}_10") (pintype "bidirectional"))
      (node (ref "L3") (pin "MP") (pinfunction "MP_MP") (pintype "passive"))
    )
    (net (code "66") (name "Net-(IC5-~{OUT4})") (class "Default")
      (node (ref "IC5") (pin "11") (pinfunction "~{OUT4}_11") (pintype "bidirectional"))
      (node (ref "L4") (pin "MP") (pinfunction "MP_MP") (pintype "passive"))
    )
    (net (code "67") (name "Net-(IC5-~{OUT5})") (class "Default")
      (node (ref "IC5") (pin "12") (pinfunction "~{OUT5}_12") (pintype "bidirectional"))
      (node (ref "L5") (pin "MP") (pinfunction "MP_MP") (pintype "passive"))
    )
    (net (code "68") (name "Net-(IC5-~{OUT6})") (class "Default")
      (node (ref "IC5") (pin "14") (pinfunction "~{OUT6}_14") (pintype "bidirectional"))
      (node (ref "L6") (pin "MP") (pinfunction "MP_MP") (pintype "passive"))
    )
    (net (code "69") (name "Net-(IC5-~{OUT7})") (class "Default")
      (node (ref "IC5") (pin "15") (pinfunction "~{OUT7}_15") (pintype "bidirectional"))
      (node (ref "L7") (pin "MP") (pinfunction "MP_MP") (pintype "passive"))
    )
    (net (code "70") (name "Net-(IC6-IP+-PadIP+@10)") (class "Default")
      (node (ref "IC6") (pin "IP+") (pinfunction "IP+_IP+") (pintype "passive"))
      (node (ref "IC6") (pin "IP+@10") (pinfunction "IP+_IP+@10") (pintype "passive"))
      (node (ref "IC6") (pin "IP+@11") (pinfunction "IP+_IP+@11") (pintype "passive"))
      (node (ref "IC6") (pin "IP+@12") (pinfunction "IP+_IP+@12") (pintype "passive"))
      (node (ref "IC6") (pin "IP+@13") (pinfunction "IP+_IP+@13") (pintype "passive"))
      (node (ref "IC6") (pin "IP+@14") (pinfunction "IP+_IP+@14") (pintype "passive"))
      (node (ref "IC6") (pin "IP+@15") (pinfunction "IP+_IP+@15") (pintype "passive"))
      (node (ref "IC6") (pin "IP+@16") (pinfunction "IP+_IP+@16") (pintype "passive"))
      (node (ref "IC6") (pin "IP+@17") (pinfunction "IP+_IP+@17") (pintype "passive"))
      (node (ref "IC6") (pin "IP+@2") (pinfunction "IP+_IP+@2") (pintype "passive"))
      (node (ref "IC6") (pin "IP+@3") (pinfunction "IP+_IP+@3") (pintype "passive"))
      (node (ref "IC6") (pin "IP+@4") (pinfunction "IP+_IP+@4") (pintype "passive"))
      (node (ref "IC6") (pin "IP+@5") (pinfunction "IP+_IP+@5") (pintype "passive"))
      (node (ref "IC6") (pin "IP+@6") (pinfunction "IP+_IP+@6") (pintype "passive"))
      (node (ref "IC6") (pin "IP+@7") (pinfunction "IP+_IP+@7") (pintype "passive"))
      (node (ref "IC6") (pin "IP+@8") (pinfunction "IP+_IP+@8") (pintype "passive"))
      (node (ref "IC6") (pin "IP+@9") (pinfunction "IP+_IP+@9") (pintype "passive"))
      (node (ref "Q1") (pin "S") (pinfunction "S_S") (pintype "passive"))
    )
    (net (code "71") (name "Net-(OK1A-A)") (class "Default")
      (node (ref "OK1") (pin "1") (pinfunction "A_1") (pintype "passive"))
      (node (ref "R25") (pin "2") (pinfunction "2_2") (pintype "passive"))
    )
    (net (code "72") (name "Net-(OK1B-A)") (class "Default")
      (node (ref "OK1") (pin "3") (pinfunction "A_3") (pintype "passive"))
      (node (ref "R26") (pin "2") (pinfunction "2_2") (pintype "passive"))
    )
    (net (code "73") (name "Net-(OK1C-A)") (class "Default")
      (node (ref "OK1") (pin "5") (pinfunction "A_5") (pintype "passive"))
      (node (ref "R27") (pin "2") (pinfunction "2_2") (pintype "passive"))
    )
    (net (code "74") (name "Net-(OK1D-A)") (class "Default")
      (node (ref "OK1") (pin "7") (pinfunction "A_7") (pintype "passive"))
      (node (ref "R28") (pin "2") (pinfunction "2_2") (pintype "passive"))
    )
    (net (code "75") (name "Net-(OK3A-A)") (class "Default")
      (node (ref "OK3") (pin "1") (pinfunction "A_1") (pintype "passive"))
      (node (ref "R10") (pin "2") (pinfunction "2_2") (pintype "passive"))
    )
    (net (code "76") (name "Net-(OK3B-A)") (class "Default")
      (node (ref "OK3") (pin "3") (pinfunction "A_3") (pintype "passive"))
      (node (ref "R11") (pin "2") (pinfunction "2_2") (pintype "passive"))
    )
    (net (code "77") (name "Net-(OK3C-A)") (class "Default")
      (node (ref "OK3") (pin "5") (pinfunction "A_5") (pintype "passive"))
      (node (ref "R12") (pin "2") (pinfunction "2_2") (pintype "passive"))
    )
    (net (code "78") (name "Net-(OK3D-A)") (class "Default")
      (node (ref "OK3") (pin "7") (pinfunction "A_7") (pintype "passive"))
      (node (ref "R13") (pin "2") (pinfunction "2_2") (pintype "passive"))
    )
    (net (code "79") (name "Net-(R3-Pad1)") (class "Default")
      (node (ref "R3") (pin "1") (pinfunction "1_1") (pintype "passive"))
      (node (ref "UBE") (pin "MP") (pinfunction "MP_MP") (pintype "passive"))
    )
    (net (code "80") (name "Net-(R5-Pad1)") (class "Default")
      (node (ref "R5") (pin "1") (pinfunction "1_1") (pintype "passive"))
      (node (ref "UCE") (pin "MP") (pinfunction "MP_MP") (pintype "passive"))
    )
    (net (code "81") (name "Net-(R7-Pad1)") (class "Default")
      (node (ref "R7") (pin "1") (pinfunction "1_1") (pintype "passive"))
      (node (ref "UAE") (pin "MP") (pinfunction "MP_MP") (pintype "passive"))
    )
    (net (code "82") (name "Net-(U$2-CH3+)") (class "Default")
      (node (ref "ADC3") (pin "MP") (pinfunction "MP_MP") (pintype "passive"))
      (node (ref "U$2") (pin "11") (pinfunction "CH3+_11") (pintype "input"))
    )
    (net (code "83") (name "Net-(U$2-CH4+)") (class "Default")
      (node (ref "ADC4") (pin "MP") (pinfunction "MP_MP") (pintype "passive"))
      (node (ref "U$2") (pin "13") (pinfunction "CH4+_13") (pintype "input"))
    )
    (net (code "84") (name "Net-(X1C-1)") (class "Default")
      (node (ref "F4") (pin "2") (pinfunction "2_2") (pintype "passive"))
      (node (ref "X1") (pin "3") (pinfunction "1_3") (pintype "passive"))
    )
    (net (code "85") (name "Net-(X1E-1)") (class "Default")
      (node (ref "F5") (pin "2") (pinfunction "2_2") (pintype "passive"))
      (node (ref "X1") (pin "5") (pinfunction "1_5") (pintype "passive"))
    )
    (net (code "86") (name "Net-(X1G-1)") (class "Default")
      (node (ref "F6") (pin "2") (pinfunction "2_2") (pintype "passive"))
      (node (ref "X1") (pin "7") (pinfunction "1_7") (pintype "passive"))
    )
    (net (code "87") (name "unconnected-(IC1-OS-Pad3)") (class "Default")
      (node (ref "IC1") (pin "3") (pinfunction "OS_3") (pintype "bidirectional"))
    )
    (net (code "88") (name "unconnected-(IC4-INT-Pad8)") (class "Default")
      (node (ref "IC4") (pin "8") (pinfunction "INT_8") (pintype "output"))
    )
    (net (code "89") (name "unconnected-(SV1-Pad1)") (class "Default")
      (node (ref "SV1") (pin "1") (pinfunction "1_1") (pintype "passive"))
    )
    (net (code "90") (name "unconnected-(SV1-Pad8)") (class "Default")
      (node (ref "SV1") (pin "8") (pinfunction "8_8") (pintype "passive"))
    )
    (net (code "91") (name "unconnected-(SV1-Pad10)") (class "Default")
      (node (ref "SV1") (pin "10") (pinfunction "10_10") (pintype "passive"))
    )
    (net (code "92") (name "unconnected-(SV1-Pad12)") (class "Default")
      (node (ref "SV1") (pin "12") (pinfunction "12_12") (pintype "passive"))
    )
    (net (code "93") (name "unconnected-(SV1-Pad17)") (class "Default")
      (node (ref "SV1") (pin "17") (pinfunction "17_17") (pintype "passive"))
    )
    (net (code "94") (name "unconnected-(SV1-Pad19)") (class "Default")
      (node (ref "SV1") (pin "19") (pinfunction "19_19") (pintype "passive"))
    )
    (net (code "95") (name "unconnected-(SV1-Pad21)") (class "Default")
      (node (ref "SV1") (pin "21") (pinfunction "21_21") (pintype "passive"))
    )
    (net (code "96") (name "unconnected-(SV1-Pad23)") (class "Default")
      (node (ref "SV1") (pin "23") (pinfunction "23_23") (pintype "passive"))
    )
    (net (code "97") (name "unconnected-(SV1-Pad24)") (class "Default")
      (node (ref "SV1") (pin "24") (pinfunction "24_24") (pintype "passive"))
    )
    (net (code "98") (name "unconnected-(SV1-Pad26)") (class "Default")
      (node (ref "SV1") (pin "26") (pinfunction "26_26") (pintype "passive"))
    )
    (net (code "99") (name "unconnected-(SV1-Pad27)") (class "Default")
      (node (ref "SV1") (pin "27") (pinfunction "27_27") (pintype "passive"))
    )
    (net (code "100") (name "unconnected-(SV1-Pad28)") (class "Default")
      (node (ref "SV1") (pin "28") (pinfunction "28_28") (pintype "passive"))
    )
    (net (code "101") (name "unconnected-(U1-CSA-Pad1)") (class "Default")
      (node (ref "U1") (pin "1") (pinfunction "CSA_1") (pintype "bidirectional"))
    )
    (net (code "102") (name "unconnected-(U1-CSB-Pad15)") (class "Default")
      (node (ref "U1") (pin "15") (pinfunction "CSB_15") (pintype "bidirectional"))
    )
    (net (code "103") (name "unconnected-(U4-CSA-Pad1)") (class "Default")
      (node (ref "U4") (pin "1") (pinfunction "CSA_1") (pintype "bidirectional"))
    )
    (net (code "104") (name "unconnected-(U4-CSB-Pad15)") (class "Default")
      (node (ref "U4") (pin "15") (pinfunction "CSB_15") (pintype "bidirectional"))
    )
  )
)
